# BrakeLines.net
KiCad netlist of a schematic drawn in Altium Designer
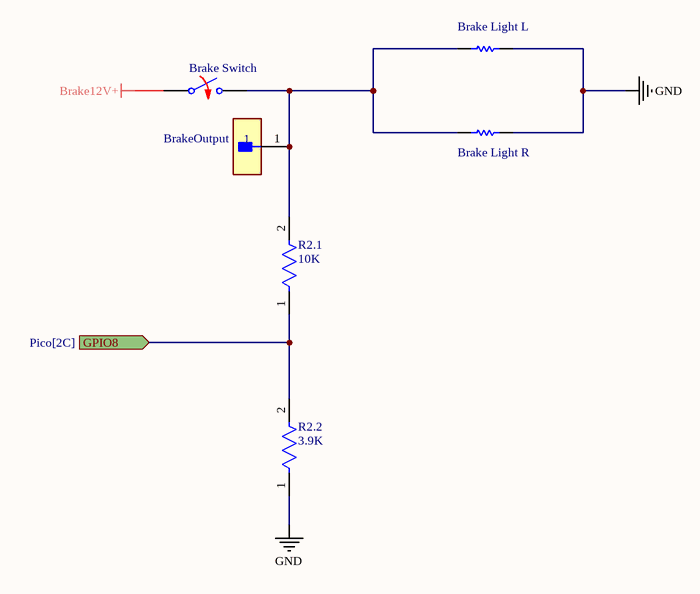
[diagram p0: BrakeLines.SchDoc]

(export (version "E")
  (design (tool "Eeschema 10.0.6"))
  (components
    (comp (ref "Brake Light L")
      (value "Resistor")
      (libsource (lib "Simulation Generic Components") (part "Resistor"))
    )
    (comp (ref "Brake Light R")
      (value "Resistor")
      (libsource (lib "Simulation Generic Components") (part "Resistor"))
    )
    (comp (ref "Brake Switch")
      (value "Brake Switch")
      (description "Switch Normally Opened")
      (libsource (lib "Simulation Generic Components") (part "SW NO"))
    )
    (comp (ref "BrakeOutput")
      (value "TSW-101-07-L-S")
      (footprint "FP-TSW-101-07-L-S-MFG")
      (description "CONN HEADER VERT 1POS")
      (libsource (lib "Altium Content Vault") (part "dd45045ce8184df9e99e12baf3f412c"))
    )
    (comp (ref "R2.1")
      (value "10K")
      (footprint "FP-MFR-12-MFG")
      (description "RES MF 1/6W 1% AXIAL")
      (fields (field (name "TOLERANCE") "1%"))
      (libsource (lib "Altium Content Vault") (part "1029c3af85768c4190bb7ad29bc67b5"))
    )
    (comp (ref "R2.2")
      (value "3.9K")
      (footprint "FP-MFR-12-MFG")
      (description "RES MF 1/6W 1% AXIAL")
      (fields (field (name "TOLERANCE") "1%"))
      (libsource (lib "Altium Content Vault") (part "1029c3af85768c4190bb7ad29bc67b5"))
    )
  )
  (nets
    (net (code "1") (name "/GPIO8") (class "Default")
      (node (ref "R2.1") (pin "1") (pinfunction "1_1") (pintype "passive"))
      (node (ref "R2.2") (pin "2") (pinfunction "2_2") (pintype "passive"))
    )
    (net (code "2") (name "Brake12V+") (class "Default")
      (node (ref "Brake Switch") (pin "1") (pinfunction "1_1") (pintype "passive"))
    )
    (net (code "3") (name "GND") (class "Default")
      (node (ref "Brake Light L") (pin "2") (pinfunction "2_2") (pintype "passive"))
      (node (ref "Brake Light R") (pin "2") (pinfunction "2_2") (pintype "passive"))
      (node (ref "R2.2") (pin "1") (pinfunction "1_1") (pintype "passive"))
    )
    (net (code "4") (name "Net-(Brake Light L-Pad1)") (class "Default")
      (node (ref "Brake Light L") (pin "1") (pinfunction "1_1") (pintype "passive"))
      (node (ref "Brake Light R") (pin "1") (pinfunction "1_1") (pintype "passive"))
      (node (ref "Brake Switch") (pin "2") (pinfunction "2_2") (pintype "passive"))
      (node (ref "BrakeOutput") (pin "1") (pinfunction "1_1") (pintype "passive"))
      (node (ref "R2.1") (pin "2") (pinfunction "2_2") (pintype "passive"))
    )
  )
)
